# ecg_biometrics.net
KiCad netlist of a schematic drawn in Altium Designer
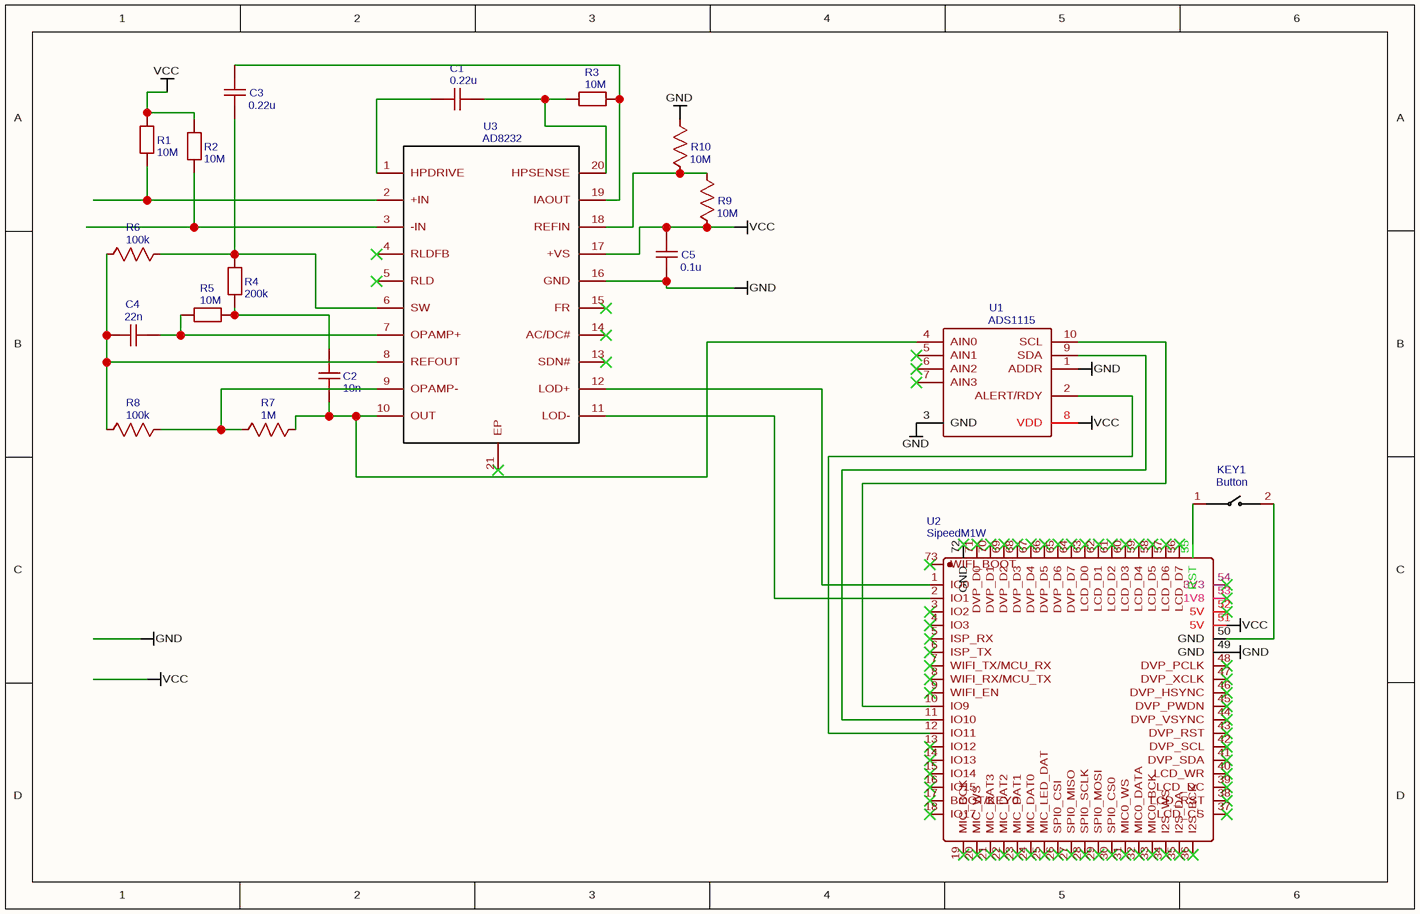
[diagram p0: ecg_biometrics.schdoc]

(export (version "E")
  (design (tool "Eeschema 10.0.6"))
  (components
    (comp (ref "C1")
      (value "0.22u")
      (fields (field (name "CONTRIBUTOR") "LCEDA_Lib"))
      (libsource (lib "altium-import") (part "root_0_0.22u_"))
    )
    (comp (ref "C2")
      (value "10n")
      (fields (field (name "CONTRIBUTOR") "LCEDA_Lib"))
      (libsource (lib "altium-import") (part "root_3_10n_"))
    )
    (comp (ref "C3")
      (value "0.22u")
      (fields (field (name "CONTRIBUTOR") "LCEDA_Lib"))
      (libsource (lib "altium-import") (part "root_3_0.22u_"))
    )
    (comp (ref "C4")
      (value "22n")
      (fields (field (name "CONTRIBUTOR") "LCEDA_Lib"))
      (libsource (lib "altium-import") (part "root_0_22n_"))
    )
    (comp (ref "C5")
      (value "0.1u")
      (fields (field (name "CONTRIBUTOR") "LCEDA_Lib"))
      (libsource (lib "altium-import") (part "root_3_0.1u_"))
    )
    (comp (ref "KEY1")
      (value "Button")
      (fields (field (name "CONTRIBUTOR") "BlackBalance"))
      (libsource (lib "altium-import") (part "root_0_Button_"))
    )
    (comp (ref "R1")
      (value "10M")
      (fields (field (name "CONTRIBUTOR") "LCEDA_Lib"))
      (libsource (lib "altium-import") (part "root_1_10M_"))
    )
    (comp (ref "R2")
      (value "10M")
      (fields (field (name "CONTRIBUTOR") "LCEDA_Lib"))
      (libsource (lib "altium-import") (part "root_1_10M_"))
    )
    (comp (ref "R3")
      (value "10M")
      (fields (field (name "CONTRIBUTOR") "LCEDA_Lib"))
      (libsource (lib "altium-import") (part "root_0_10M_"))
    )
    (comp (ref "R4")
      (value "200k")
      (fields (field (name "CONTRIBUTOR") "LCEDA_Lib"))
      (libsource (lib "altium-import") (part "root_1_200k_"))
    )
    (comp (ref "R5")
      (value "10M")
      (fields (field (name "CONTRIBUTOR") "LCEDA_Lib"))
      (libsource (lib "altium-import") (part "root_0_10M_"))
    )
    (comp (ref "R6")
      (value "100k")
      (fields (field (name "CONTRIBUTOR") "LCEDA_Lib"))
      (libsource (lib "altium-import") (part "root_0_100k_"))
    )
    (comp (ref "R7")
      (value "1M")
      (fields (field (name "CONTRIBUTOR") "LCEDA_Lib"))
      (libsource (lib "altium-import") (part "root_0_1M_"))
    )
    (comp (ref "R8")
      (value "100k")
      (fields (field (name "CONTRIBUTOR") "LCEDA_Lib"))
      (libsource (lib "altium-import") (part "root_0_100k_"))
    )
    (comp (ref "R9")
      (value "10M")
      (fields (field (name "CONTRIBUTOR") "LCEDA_Lib"))
      (libsource (lib "") (part "root_1_10M__1"))
    )
    (comp (ref "R10")
      (value "10M")
      (fields (field (name "CONTRIBUTOR") "LCEDA_Lib"))
      (libsource (lib "") (part "root_1_10M__1"))
    )
    (comp (ref "U1")
      (value "ADS1115")
      (fields
        (field (name "BOM_MANUFACTURER PART") "ADS1115IDGSR")
        (field (name "BOM_SUPPLIER PART") "C37593")
      )
      (libsource (lib "altium-import") (part "root_0_ADS1115_"))
    )
    (comp (ref "U2")
      (value "SipeedM1W")
      (fields (field (name "BOM_MANUFACTURER PART") "M1W") (field (name "CONTRIBUTOR") "comdet"))
      (libsource (lib "altium-import") (part "root_0_SipeedM1W_"))
    )
    (comp (ref "U3")
      (value "AD8232")
      (fields
        (field (name "BOM_MANUFACTURER PART") "AD8232ACPZ-R7")
        (field (name "BOM_SUPPLIER PART") "C43216")
        (field (name "CONTRIBUTOR") "alexgubanow")
      )
      (libsource (lib "altium-import") (part "root_0_AD8232_"))
    )
  )
  (nets
    (net (code "1") (name "GND") (class "Default")
      (node (ref "C5") (pin "2") (pinfunction "2_2") (pintype "passive"))
      (node (ref "R10") (pin "2") (pinfunction "2_2") (pintype "passive"))
      (node (ref "U1") (pin "1") (pinfunction "ADDR_1") (pintype "passive"))
      (node (ref "U1") (pin "3") (pinfunction "GND_3") (pintype "passive"))
      (node (ref "U2") (pin "49") (pinfunction "GND_49") (pintype "passive"))
      (node (ref "U3") (pin "16") (pinfunction "GND_16") (pintype "passive"))
    )
    (net (code "2") (name "Net-(C2-Pad1)") (class "Default")
      (node (ref "C2") (pin "1") (pinfunction "1_1") (pintype "passive"))
      (node (ref "R4") (pin "1") (pinfunction "1_1") (pintype "passive"))
      (node (ref "R5") (pin "2") (pinfunction "2_2") (pintype "passive"))
    )
    (net (code "3") (name "Net-(KEY1-Pad2)") (class "Default")
      (node (ref "KEY1") (pin "2") (pinfunction "2_2") (pintype "passive"))
      (node (ref "U2") (pin "50") (pinfunction "GND_50") (pintype "passive"))
    )
    (net (code "4") (name "Net-(U1-AIN0)") (class "Default")
      (node (ref "C2") (pin "2") (pinfunction "2_2") (pintype "passive"))
      (node (ref "R7") (pin "2") (pinfunction "2_2") (pintype "passive"))
      (node (ref "U1") (pin "4") (pinfunction "AIN0_4") (pintype "passive"))
      (node (ref "U3") (pin "10") (pinfunction "OUT_10") (pintype "passive"))
    )
    (net (code "5") (name "Net-(U1-ALERT{slash}RDY)") (class "Default")
      (node (ref "U1") (pin "2") (pinfunction "ALERT/RDY_2") (pintype "passive"))
      (node (ref "U2") (pin "12") (pinfunction "IO11_12") (pintype "passive"))
    )
    (net (code "6") (name "Net-(U1-SCL)") (class "Default")
      (node (ref "U1") (pin "10") (pinfunction "SCL_10") (pintype "passive"))
      (node (ref "U2") (pin "10") (pinfunction "IO9_10") (pintype "passive"))
    )
    (net (code "7") (name "Net-(U1-SDA)") (class "Default")
      (node (ref "U1") (pin "9") (pinfunction "SDA_9") (pintype "passive"))
      (node (ref "U2") (pin "11") (pinfunction "IO10_11") (pintype "passive"))
    )
    (net (code "8") (name "Net-(U2-IO0)") (class "Default")
      (node (ref "U2") (pin "1") (pinfunction "IO0_1") (pintype "passive"))
      (node (ref "U3") (pin "12") (pinfunction "LOD+_12") (pintype "passive"))
    )
    (net (code "9") (name "Net-(U2-IO1)") (class "Default")
      (node (ref "U2") (pin "2") (pinfunction "IO1_2") (pintype "passive"))
      (node (ref "U3") (pin "11") (pinfunction "LOD-_11") (pintype "passive"))
    )
    (net (code "10") (name "Net-(U2-RST)") (class "Default")
      (node (ref "KEY1") (pin "1") (pinfunction "1_1") (pintype "passive"))
      (node (ref "U2") (pin "55") (pinfunction "RST_55") (pintype "passive"))
    )
    (net (code "11") (name "Net-(U3-+IN)") (class "Default")
      (node (ref "R1") (pin "1") (pinfunction "1_1") (pintype "passive"))
      (node (ref "U3") (pin "2") (pinfunction "+IN_2") (pintype "passive"))
    )
    (net (code "12") (name "Net-(U3--IN)") (class "Default")
      (node (ref "R2") (pin "1") (pinfunction "1_1") (pintype "passive"))
      (node (ref "U3") (pin "3") (pinfunction "-IN_3") (pintype "passive"))
    )
    (net (code "13") (name "Net-(U3-HPDRIVE)") (class "Default")
      (node (ref "C1") (pin "1") (pinfunction "1_1") (pintype "passive"))
      (node (ref "U3") (pin "1") (pinfunction "HPDRIVE_1") (pintype "passive"))
    )
    (net (code "14") (name "Net-(U3-HPSENSE)") (class "Default")
      (node (ref "C1") (pin "2") (pinfunction "2_2") (pintype "passive"))
      (node (ref "R3") (pin "1") (pinfunction "1_1") (pintype "passive"))
      (node (ref "U3") (pin "20") (pinfunction "HPSENSE_20") (pintype "passive"))
    )
    (net (code "15") (name "Net-(U3-IAOUT)") (class "Default")
      (node (ref "C3") (pin "1") (pinfunction "1_1") (pintype "passive"))
      (node (ref "R3") (pin "2") (pinfunction "2_2") (pintype "passive"))
      (node (ref "U3") (pin "19") (pinfunction "IAOUT_19") (pintype "passive"))
    )
    (net (code "16") (name "Net-(U3-OPAMP+)") (class "Default")
      (node (ref "C4") (pin "2") (pinfunction "2_2") (pintype "passive"))
      (node (ref "R5") (pin "1") (pinfunction "1_1") (pintype "passive"))
      (node (ref "U3") (pin "7") (pinfunction "OPAMP+_7") (pintype "passive"))
    )
    (net (code "17") (name "Net-(U3-OPAMP-)") (class "Default")
      (node (ref "R7") (pin "1") (pinfunction "1_1") (pintype "passive"))
      (node (ref "R8") (pin "2") (pinfunction "2_2") (pintype "passive"))
      (node (ref "U3") (pin "9") (pinfunction "OPAMP-_9") (pintype "passive"))
    )
    (net (code "18") (name "Net-(U3-REFIN)") (class "Default")
      (node (ref "R10") (pin "1") (pinfunction "1_1") (pintype "passive"))
      (node (ref "R9") (pin "2") (pinfunction "2_2") (pintype "passive"))
      (node (ref "U3") (pin "18") (pinfunction "REFIN_18") (pintype "passive"))
    )
    (net (code "19") (name "Net-(U3-REFOUT)") (class "Default")
      (node (ref "C4") (pin "1") (pinfunction "1_1") (pintype "passive"))
      (node (ref "R6") (pin "1") (pinfunction "1_1") (pintype "passive"))
      (node (ref "R8") (pin "1") (pinfunction "1_1") (pintype "passive"))
      (node (ref "U3") (pin "8") (pinfunction "REFOUT_8") (pintype "passive"))
    )
    (net (code "20") (name "Net-(U3-SW)") (class "Default")
      (node (ref "C3") (pin "2") (pinfunction "2_2") (pintype "passive"))
      (node (ref "R4") (pin "2") (pinfunction "2_2") (pintype "passive"))
      (node (ref "R6") (pin "2") (pinfunction "2_2") (pintype "passive"))
      (node (ref "U3") (pin "6") (pinfunction "SW_6") (pintype "passive"))
    )
    (net (code "21") (name "VCC") (class "Default")
      (node (ref "C5") (pin "1") (pinfunction "1_1") (pintype "passive"))
      (node (ref "R1") (pin "2") (pinfunction "2_2") (pintype "passive"))
      (node (ref "R2") (pin "2") (pinfunction "2_2") (pintype "passive"))
      (node (ref "R9") (pin "1") (pinfunction "1_1") (pintype "passive"))
      (node (ref "U1") (pin "8") (pinfunction "VDD_8") (pintype "passive"))
      (node (ref "U2") (pin "51") (pinfunction "5V_51") (pintype "passive"))
      (node (ref "U3") (pin "17") (pinfunction "+VS_17") (pintype "passive"))
    )
    (net (code "22") (name "unconnected-(U1-AIN1-Pad5)") (class "Default")
      (node (ref "U1") (pin "5") (pinfunction "AIN1_5") (pintype "passive+no_connect"))
    )
    (net (code "23") (name "unconnected-(U1-AIN2-Pad6)") (class "Default")
      (node (ref "U1") (pin "6") (pinfunction "AIN2_6") (pintype "passive+no_connect"))
    )
    (net (code "24") (name "unconnected-(U1-AIN3-Pad7)") (class "Default")
      (node (ref "U1") (pin "7") (pinfunction "AIN3_7") (pintype "passive+no_connect"))
    )
    (net (code "25") (name "unconnected-(U2-1V8-Pad53)") (class "Default")
      (node (ref "U2") (pin "53") (pinfunction "1V8_53") (pintype "passive+no_connect"))
    )
    (net (code "26") (name "unconnected-(U2-3V3-Pad54)") (class "Default")
      (node (ref "U2") (pin "54") (pinfunction "3V3_54") (pintype "passive+no_connect"))
    )
    (net (code "27") (name "unconnected-(U2-5V-Pad52)") (class "Default")
      (node (ref "U2") (pin "52") (pinfunction "5V_52") (pintype "passive+no_connect"))
    )
    (net (code "28") (name "unconnected-(U2-BOOT{slash}KEY0-Pad17)") (class "Default")
      (node (ref "U2") (pin "17") (pinfunction "BOOT/KEY0_17") (pintype "passive+no_connect"))
    )
    (net (code "29") (name "unconnected-(U2-DVP_D0-Pad71)") (class "Default")
      (node (ref "U2") (pin "71") (pinfunction "DVP_D0_71") (pintype "passive+no_connect"))
    )
    (net (code "30") (name "unconnected-(U2-DVP_D1-Pad70)") (class "Default")
      (node (ref "U2") (pin "70") (pinfunction "DVP_D1_70") (pintype "passive+no_connect"))
    )
    (net (code "31") (name "unconnected-(U2-DVP_D2-Pad69)") (class "Default")
      (node (ref "U2") (pin "69") (pinfunction "DVP_D2_69") (pintype "passive+no_connect"))
    )
    (net (code "32") (name "unconnected-(U2-DVP_D3-Pad68)") (class "Default")
      (node (ref "U2") (pin "68") (pinfunction "DVP_D3_68") (pintype "passive+no_connect"))
    )
    (net (code "33") (name "unconnected-(U2-DVP_D4-Pad67)") (class "Default")
      (node (ref "U2") (pin "67") (pinfunction "DVP_D4_67") (pintype "passive+no_connect"))
    )
    (net (code "34") (name "unconnected-(U2-DVP_D5-Pad66)") (class "Default")
      (node (ref "U2") (pin "66") (pinfunction "DVP_D5_66") (pintype "passive+no_connect"))
    )
    (net (code "35") (name "unconnected-(U2-DVP_D6-Pad65)") (class "Default")
      (node (ref "U2") (pin "65") (pinfunction "DVP_D6_65") (pintype "passive+no_connect"))
    )
    (net (code "36") (name "unconnected-(U2-DVP_D7-Pad64)") (class "Default")
      (node (ref "U2") (pin "64") (pinfunction "DVP_D7_64") (pintype "passive+no_connect"))
    )
    (net (code "37") (name "unconnected-(U2-DVP_HSYNC-Pad46)") (class "Default")
      (node (ref "U2") (pin "46") (pinfunction "DVP_HSYNC_46") (pintype "passive+no_connect"))
    )
    (net (code "38") (name "unconnected-(U2-DVP_PCLK-Pad48)") (class "Default")
      (node (ref "U2") (pin "48") (pinfunction "DVP_PCLK_48") (pintype "passive+no_connect"))
    )
    (net (code "39") (name "unconnected-(U2-DVP_PWDN-Pad45)") (class "Default")
      (node (ref "U2") (pin "45") (pinfunction "DVP_PWDN_45") (pintype "passive+no_connect"))
    )
    (net (code "40") (name "unconnected-(U2-DVP_RST-Pad43)") (class "Default")
      (node (ref "U2") (pin "43") (pinfunction "DVP_RST_43") (pintype "passive+no_connect"))
    )
    (net (code "41") (name "unconnected-(U2-DVP_SCL-Pad42)") (class "Default")
      (node (ref "U2") (pin "42") (pinfunction "DVP_SCL_42") (pintype "passive+no_connect"))
    )
    (net (code "42") (name "unconnected-(U2-DVP_SDA-Pad41)") (class "Default")
      (node (ref "U2") (pin "41") (pinfunction "DVP_SDA_41") (pintype "passive+no_connect"))
    )
    (net (code "43") (name "unconnected-(U2-DVP_VSYNC-Pad44)") (class "Default")
      (node (ref "U2") (pin "44") (pinfunction "DVP_VSYNC_44") (pintype "passive+no_connect"))
    )
    (net (code "44") (name "unconnected-(U2-DVP_XCLK-Pad47)") (class "Default")
      (node (ref "U2") (pin "47") (pinfunction "DVP_XCLK_47") (pintype "passive+no_connect"))
    )
    (net (code "45") (name "unconnected-(U2-GND-Pad72)") (class "Default")
      (node (ref "U2") (pin "72") (pinfunction "GND_72") (pintype "passive+no_connect"))
    )
    (net (code "46") (name "unconnected-(U2-I2S_BCK-Pad36)") (class "Default")
      (node (ref "U2") (pin "36") (pinfunction "I2S_BCK_36") (pintype "passive+no_connect"))
    )
    (net (code "47") (name "unconnected-(U2-I2S_DA-Pad35)") (class "Default")
      (node (ref "U2") (pin "35") (pinfunction "I2S_DA_35") (pintype "passive+no_connect"))
    )
    (net (code "48") (name "unconnected-(U2-I2S_WS-Pad34)") (class "Default")
      (node (ref "U2") (pin "34") (pinfunction "I2S_WS_34") (pintype "passive+no_connect"))
    )
    (net (code "49") (name "unconnected-(U2-IO2-Pad3)") (class "Default")
      (node (ref "U2") (pin "3") (pinfunction "IO2_3") (pintype "passive+no_connect"))
    )
    (net (code "50") (name "unconnected-(U2-IO3-Pad4)") (class "Default")
      (node (ref "U2") (pin "4") (pinfunction "IO3_4") (pintype "passive+no_connect"))
    )
    (net (code "51") (name "unconnected-(U2-IO12-Pad13)") (class "Default")
      (node (ref "U2") (pin "13") (pinfunction "IO12_13") (pintype "passive+no_connect"))
    )
    (net (code "52") (name "unconnected-(U2-IO13-Pad14)") (class "Default")
      (node (ref "U2") (pin "14") (pinfunction "IO13_14") (pintype "passive+no_connect"))
    )
    (net (code "53") (name "unconnected-(U2-IO14-Pad15)") (class "Default")
      (node (ref "U2") (pin "15") (pinfunction "IO14_15") (pintype "passive+no_connect"))
    )
    (net (code "54") (name "unconnected-(U2-IO15-Pad16)") (class "Default")
      (node (ref "U2") (pin "16") (pinfunction "IO15_16") (pintype "passive+no_connect"))
    )
    (net (code "55") (name "unconnected-(U2-IO17-Pad18)") (class "Default")
      (node (ref "U2") (pin "18") (pinfunction "IO17_18") (pintype "passive+no_connect"))
    )
    (net (code "56") (name "unconnected-(U2-ISP_RX-Pad5)") (class "Default")
      (node (ref "U2") (pin "5") (pinfunction "ISP_RX_5") (pintype "passive+no_connect"))
    )
    (net (code "57") (name "unconnected-(U2-ISP_TX-Pad6)") (class "Default")
      (node (ref "U2") (pin "6") (pinfunction "ISP_TX_6") (pintype "passive+no_connect"))
    )
    (net (code "58") (name "unconnected-(U2-LCD_CS-Pad37)") (class "Default")
      (node (ref "U2") (pin "37") (pinfunction "LCD_CS_37") (pintype "passive+no_connect"))
    )
    (net (code "59") (name "unconnected-(U2-LCD_D0-Pad63)") (class "Default")
      (node (ref "U2") (pin "63") (pinfunction "LCD_D0_63") (pintype "passive+no_connect"))
    )
    (net (code "60") (name "unconnected-(U2-LCD_D1-Pad62)") (class "Default")
      (node (ref "U2") (pin "62") (pinfunction "LCD_D1_62") (pintype "passive+no_connect"))
    )
    (net (code "61") (name "unconnected-(U2-LCD_D2-Pad61)") (class "Default")
      (node (ref "U2") (pin "61") (pinfunction "LCD_D2_61") (pintype "passive+no_connect"))
    )
    (net (code "62") (name "unconnected-(U2-LCD_D3-Pad60)") (class "Default")
      (node (ref "U2") (pin "60") (pinfunction "LCD_D3_60") (pintype "passive+no_connect"))
    )
    (net (code "63") (name "unconnected-(U2-LCD_D4-Pad59)") (class "Default")
      (node (ref "U2") (pin "59") (pinfunction "LCD_D4_59") (pintype "passive+no_connect"))
    )
    (net (code "64") (name "unconnected-(U2-LCD_D5-Pad58)") (class "Default")
      (node (ref "U2") (pin "58") (pinfunction "LCD_D5_58") (pintype "passive+no_connect"))
    )
    (net (code "65") (name "unconnected-(U2-LCD_D6-Pad57)") (class "Default")
      (node (ref "U2") (pin "57") (pinfunction "LCD_D6_57") (pintype "passive+no_connect"))
    )
    (net (code "66") (name "unconnected-(U2-LCD_D7-Pad56)") (class "Default")
      (node (ref "U2") (pin "56") (pinfunction "LCD_D7_56") (pintype "passive+no_connect"))
    )
    (net (code "67") (name "unconnected-(U2-LCD_DC-Pad39)") (class "Default")
      (node (ref "U2") (pin "39") (pinfunction "LCD_DC_39") (pintype "passive+no_connect"))
    )
    (net (code "68") (name "unconnected-(U2-LCD_RST-Pad38)") (class "Default")
      (node (ref "U2") (pin "38") (pinfunction "LCD_RST_38") (pintype "passive+no_connect"))
    )
    (net (code "69") (name "unconnected-(U2-LCD_WR-Pad40)") (class "Default")
      (node (ref "U2") (pin "40") (pinfunction "LCD_WR_40") (pintype "passive+no_connect"))
    )
    (net (code "70") (name "unconnected-(U2-MIC0_BCK-Pad33)") (class "Default")
      (node (ref "U2") (pin "33") (pinfunction "MIC0_BCK_33") (pintype "passive+no_connect"))
    )
    (net (code "71") (name "unconnected-(U2-MIC0_DATA-Pad32)") (class "Default")
      (node (ref "U2") (pin "32") (pinfunction "MIC0_DATA_32") (pintype "passive+no_connect"))
    )
    (net (code "72") (name "unconnected-(U2-MIC0_WS-Pad31)") (class "Default")
      (node (ref "U2") (pin "31") (pinfunction "MIC0_WS_31") (pintype "passive+no_connect"))
    )
    (net (code "73") (name "unconnected-(U2-MIC_BCK-Pad19)") (class "Default")
      (node (ref "U2") (pin "19") (pinfunction "MIC_BCK_19") (pintype "passive+no_connect"))
    )
    (net (code "74") (name "unconnected-(U2-MIC_DAT0-Pad24)") (class "Default")
      (node (ref "U2") (pin "24") (pinfunction "MIC_DAT0_24") (pintype "passive+no_connect"))
    )
    (net (code "75") (name "unconnected-(U2-MIC_DAT1-Pad23)") (class "Default")
      (node (ref "U2") (pin "23") (pinfunction "MIC_DAT1_23") (pintype "passive+no_connect"))
    )
    (net (code "76") (name "unconnected-(U2-MIC_DAT2-Pad22)") (class "Default")
      (node (ref "U2") (pin "22") (pinfunction "MIC_DAT2_22") (pintype "passive+no_connect"))
    )
    (net (code "77") (name "unconnected-(U2-MIC_DAT3-Pad21)") (class "Default")
      (node (ref "U2") (pin "21") (pinfunction "MIC_DAT3_21") (pintype "passive+no_connect"))
    )
    (net (code "78") (name "unconnected-(U2-MIC_LED_DAT-Pad25)") (class "Default")
      (node (ref "U2") (pin "25") (pinfunction "MIC_LED_DAT_25") (pintype "passive+no_connect"))
    )
    (net (code "79") (name "unconnected-(U2-MIC_WS-Pad20)") (class "Default")
      (node (ref "U2") (pin "20") (pinfunction "MIC_WS_20") (pintype "passive+no_connect"))
    )
    (net (code "80") (name "unconnected-(U2-SPI0_CS0-Pad30)") (class "Default")
      (node (ref "U2") (pin "30") (pinfunction "SPI0_CS0_30") (pintype "passive+no_connect"))
    )
    (net (code "81") (name "unconnected-(U2-SPI0_CSI-Pad26)") (class "Default")
      (node (ref "U2") (pin "26") (pinfunction "SPI0_CSI_26") (pintype "passive+no_connect"))
    )
    (net (code "82") (name "unconnected-(U2-SPI0_MISO-Pad27)") (class "Default")
      (node (ref "U2") (pin "27") (pinfunction "SPI0_MISO_27") (pintype "passive+no_connect"))
    )
    (net (code "83") (name "unconnected-(U2-SPI0_MOSI-Pad29)") (class "Default")
      (node (ref "U2") (pin "29") (pinfunction "SPI0_MOSI_29") (pintype "passive+no_connect"))
    )
    (net (code "84") (name "unconnected-(U2-SPI0_SCLK-Pad28)") (class "Default")
      (node (ref "U2") (pin "28") (pinfunction "SPI0_SCLK_28") (pintype "passive+no_connect"))
    )
    (net (code "85") (name "unconnected-(U2-WIFI_BOOT-Pad73)") (class "Default")
      (node (ref "U2") (pin "73") (pinfunction "WIFI_BOOT_73") (pintype "passive+no_connect"))
    )
    (net (code "86") (name "unconnected-(U2-WIFI_EN-Pad9)") (class "Default")
      (node (ref "U2") (pin "9") (pinfunction "WIFI_EN_9") (pintype "passive+no_connect"))
    )
    (net (code "87") (name "unconnected-(U2-WIFI_RX{slash}MCU_TX-Pad8)") (class "Default")
      (node (ref "U2") (pin "8") (pinfunction "WIFI_RX/MCU_TX_8") (pintype "passive+no_connect"))
    )
    (net (code "88") (name "unconnected-(U2-WIFI_TX{slash}MCU_RX-Pad7)") (class "Default")
      (node (ref "U2") (pin "7") (pinfunction "WIFI_TX/MCU_RX_7") (pintype "passive+no_connect"))
    )
    (net (code "89") (name "unconnected-(U3-AC{slash}DC#-Pad14)") (class "Default")
      (node (ref "U3") (pin "14") (pinfunction "AC/DC#_14") (pintype "passive+no_connect"))
    )
    (net (code "90") (name "unconnected-(U3-EP-Pad21)") (class "Default")
      (node (ref "U3") (pin "21") (pinfunction "EP_21") (pintype "passive+no_connect"))
    )
    (net (code "91") (name "unconnected-(U3-FR-Pad15)") (class "Default")
      (node (ref "U3") (pin "15") (pinfunction "FR_15") (pintype "passive+no_connect"))
    )
    (net (code "92") (name "unconnected-(U3-RLD-Pad5)") (class "Default")
      (node (ref "U3") (pin "5") (pinfunction "RLD_5") (pintype "passive+no_connect"))
    )
    (net (code "93") (name "unconnected-(U3-RLDFB-Pad4)") (class "Default")
      (node (ref "U3") (pin "4") (pinfunction "RLDFB_4") (pintype "passive+no_connect"))
    )
    (net (code "94") (name "unconnected-(U3-SDN#-Pad13)") (class "Default")
      (node (ref "U3") (pin "13") (pinfunction "SDN#_13") (pintype "passive+no_connect"))
    )
  )
)
